# RS485.net
KiCad netlist of a schematic drawn in Altium Designer
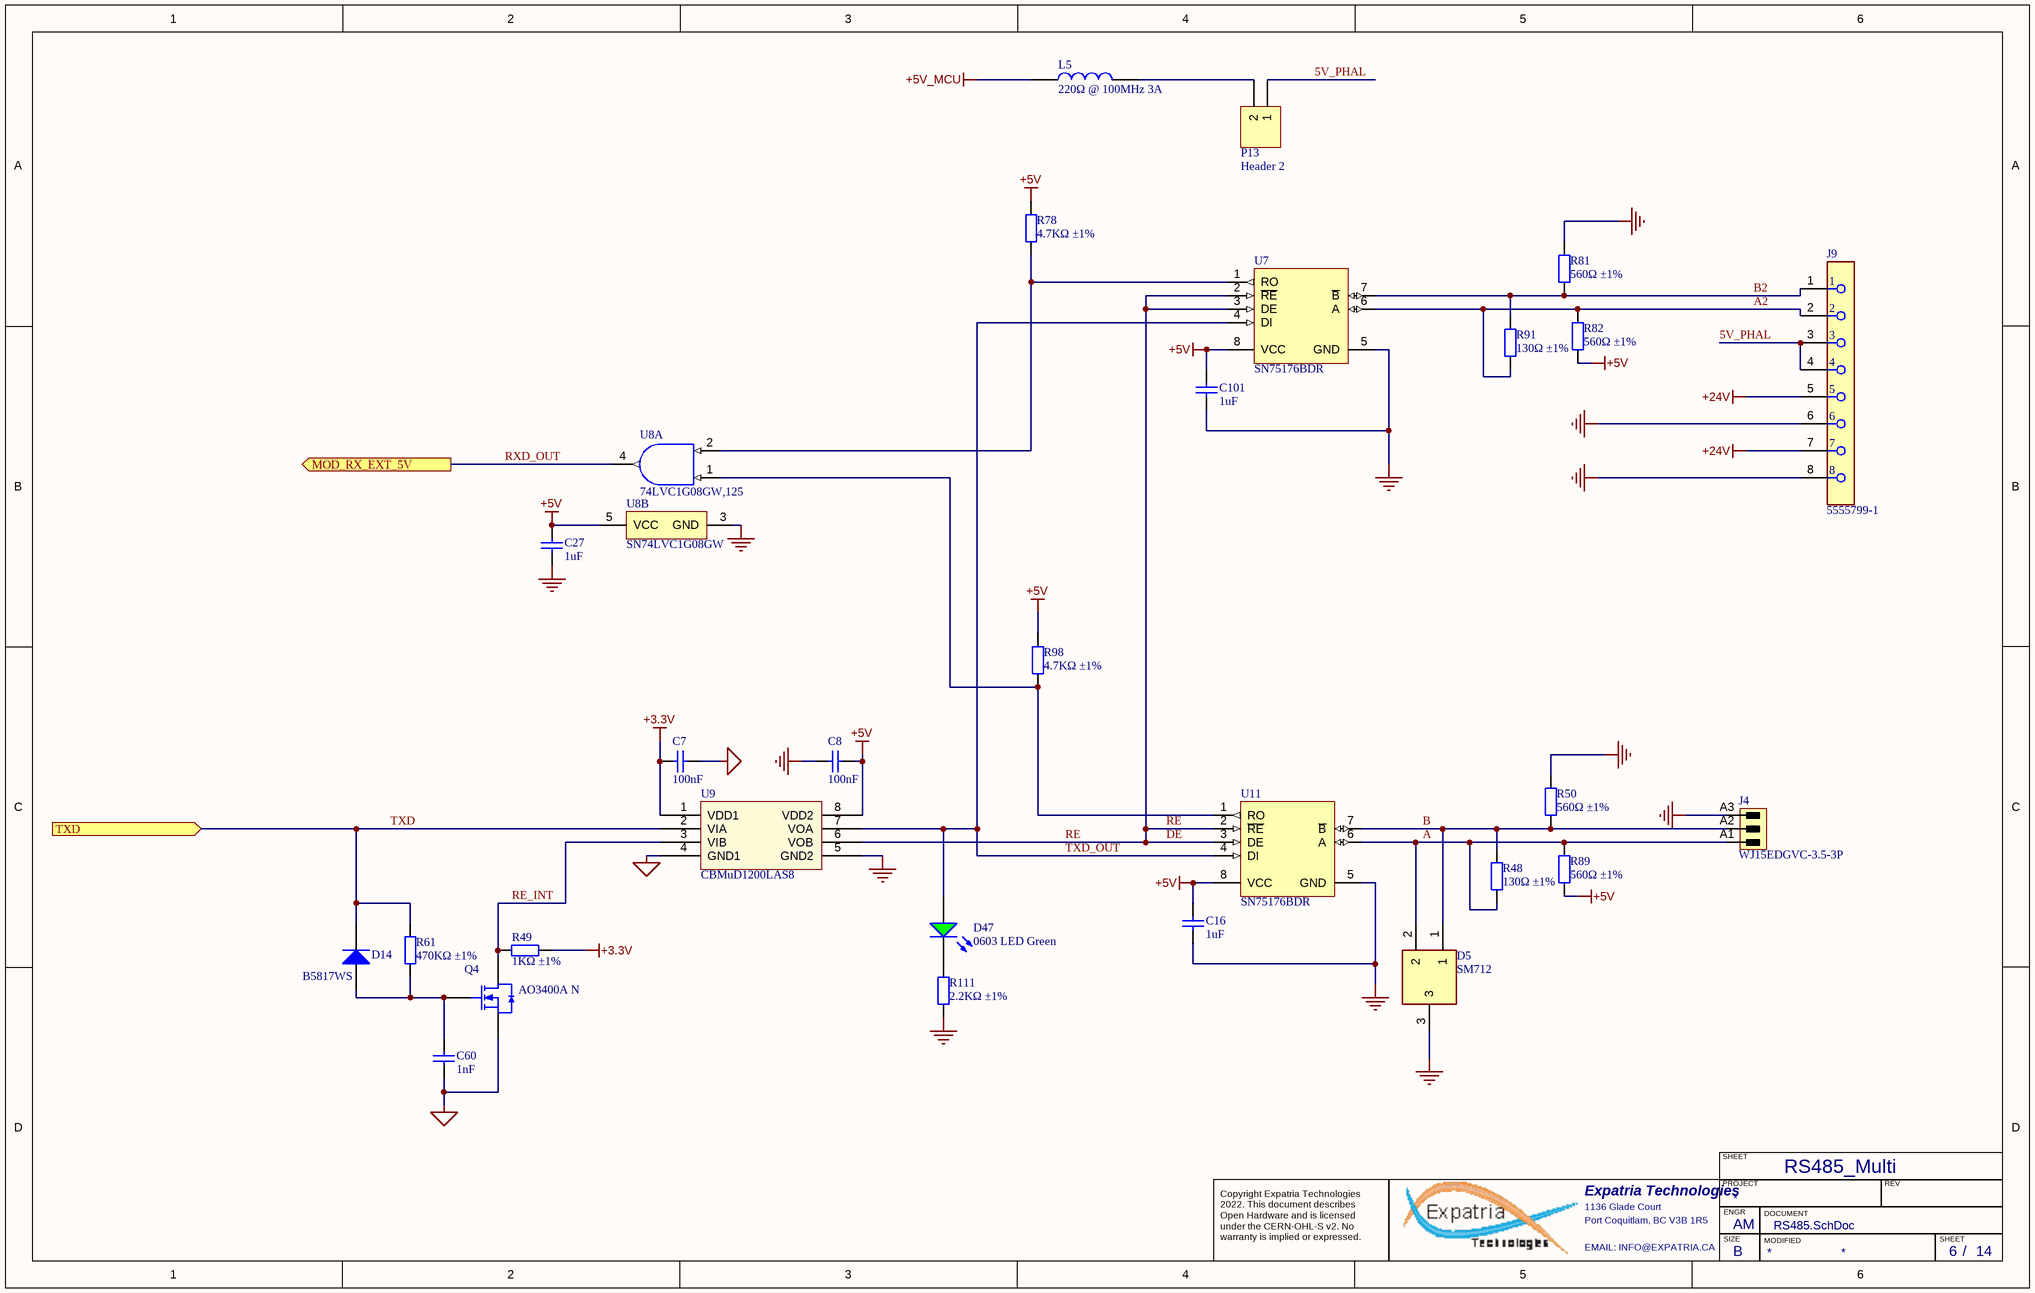
[diagram p0: RS485.SchDoc]

(export (version "E")
  (design (tool "Eeschema 10.0.6"))
  (components
    (comp (ref "C7")
      (value "100nF")
      (footprint "0402_C")
      (description "Chip capacitors")
      (fields
        (field (name "MANUFACTURER") "Samsung Electro-Mechanics")
        (field (name "PARTNUMBER") "CL05B104KO5NNNC")
      )
      (libsource (lib "Cap") (part "0402 100nF (104) 10% 16V"))
    )
    (comp (ref "C8")
      (value "100nF")
      (footprint "0402_C")
      (description "Chip capacitors")
      (fields
        (field (name "MANUFACTURER") "Samsung Electro-Mechanics")
        (field (name "PARTNUMBER") "CL05B104KO5NNNC")
      )
      (libsource (lib "Cap") (part "0402 100nF (104) 10% 16V"))
    )
    (comp (ref "C16")
      (value "1uF")
      (footprint "0603_C")
      (description "Chip capacitors")
      (fields
        (field (name "MANUFACTURER") "Samsung Electro-Mechanics")
        (field (name "PARTNUMBER") "CL10A105KB8NNNC")
      )
      (libsource (lib "Cap") (part "0603 1uF (105) 10% 50V"))
    )
    (comp (ref "C27")
      (value "1uF")
      (footprint "0603_C")
      (description "Chip capacitors")
      (fields
        (field (name "MANUFACTURER") "Samsung Electro-Mechanics")
        (field (name "PARTNUMBER") "CL10A105KB8NNNC")
      )
      (libsource (lib "Cap") (part "0603 1uF (105) 10% 50V"))
    )
    (comp (ref "C60")
      (value "1nF")
      (footprint "0603_C")
      (description "Chip capacitors")
      (fields
        (field (name "MANUFACTURER") "Samsung Electro-Mechanics")
        (field (name "PARTNUMBER") "CL10B102KB8NNNC")
      )
      (libsource (lib "Cap") (part "0603 1nF (102) 10% 50V"))
    )
    (comp (ref "C101")
      (value "1uF")
      (footprint "0603_C")
      (description "Chip capacitors")
      (fields
        (field (name "MANUFACTURER") "Samsung Electro-Mechanics")
        (field (name "PARTNUMBER") "CL10A105KB8NNNC")
      )
      (libsource (lib "Cap") (part "0603 1uF (105) 10% 50V"))
    )
    (comp (ref "D5")
      (value "SM712")
      (footprint "SamacSys:SOT95P230X117-3N")
      (description "Bidirectional 12V (Max), 7V (Max) 7.5V / 13.3V 10V / 20V 12A(8/20us) SOT-23-3 TVS RoHS")
      (libsource (lib "*") (part "CDSOT23-SM712"))
    )
    (comp (ref "D14")
      (value "B5817WS")
      (footprint "SOD-323")
      (description "20V 750mV@3A 1A SOD-323 Schottky Barrier Diodes (SBD) ROHS")
      (libsource (lib "Diode") (part "SOD-123 B5819W  SL"))
    )
    (comp (ref "D47")
      (value "0603 LED Green")
      (footprint "0603_LED_S1 - GREEN")
      (fields
        (field (name "MANUFACTURER PART NUMBER") "19-217/GHC-YR1S2/3T")
        (field (name "MANUFACTURER") "Everlight Elec")
      )
      (libsource (lib "Sienci_Labs") (part "19-217/GHC-YR1S2/3T"))
    )
    (comp (ref "J4")
      (value "WJ15EDGVC-3.5-3P")
      (footprint "691321100003 - 3.5mm  3p")
      (fields (field (name "MANUFACTURER") "Ningbo Kangnex Elec"))
      (libsource (lib "Universal_CNC_Breakout") (part "3.5mm Terminal Header 3p"))
    )
    (comp (ref "J9")
      (value "5555799-1")
      (footprint "FP-5555799-1-MFG")
      (description "CONN MOD JACK 8P8C VERT UNSHLD")
      (fields
        (field (name "MANUFACTURER") "TE Connectivity")
        (field (name "OCTOPART") "https://octopart.com/5555799-1-te+connectivity-39526335")
      )
      (libsource (lib "PrintNC_GRBLHAL_Breakout") (part "a32a9c29f5c2290c50060dfb8ad7212"))
    )
    (comp (ref "L5")
      (value "220Ω @ 100MHz 3A")
      (footprint "0805_C")
      (description "40mΩ ±25% 220Ω@100MHz 0805 Ferrite Beads ROHS")
      (libsource (lib "FBEAD") (part "0402 220R@100Mhz 0.1A"))
    )
    (comp (ref "P13")
      (value "Header 2")
      (footprint "HDR1X2")
      (description "Header, 2-Pin")
      (fields (field (name "PUBLISHER") "Altium Limited"))
      (libsource (lib "Miscellaneous Connectors") (part "Header 2"))
    )
    (comp (ref "Q4")
      (value "AO3400A N")
      (footprint "SOT-23-3L")
      (description "MOS(场效应管)")
      (libsource (lib "MOS") (part "AO3400A N道沟 X0YV1T SOT-23"))
    )
    (comp (ref "R48")
      (value "130Ω ±1%")
      (footprint "0603_R")
      (description "Chip resistor")
      (fields (field (name "MANUFACTURER") "Uniroyal Elec") (field (name "PARTNUMBER") "0603WAF1300T5E"))
      (libsource (lib "RES") (part "0603 130R (1300) 1%"))
    )
    (comp (ref "R49")
      (value "1KΩ ±1%")
      (footprint "0402_R")
      (description "Chip resistor")
      (fields (field (name "MANUFACTURER") "Uniroyal Elec") (field (name "PARTNUMBER") "0402WGF1001TCE"))
      (libsource (lib "RES") (part "0402 1K (1001) 1%"))
    )
    (comp (ref "R50")
      (value "560Ω ±1%")
      (footprint "0603_R")
      (description "Chip resistor")
      (fields (field (name "MANUFACTURER") "Uniroyal Elec") (field (name "PARTNUMBER") "0603WAF5600T5E"))
      (libsource (lib "RES") (part "0603 560R (5600) 1%"))
    )
    (comp (ref "R61")
      (value "470KΩ ±1%")
      (footprint "0603_R")
      (description "Chip resistor")
      (fields (field (name "MANUFACTURER") "Uniroyal Elec") (field (name "PARTNUMBER") "0603WAF4703T5E"))
      (libsource (lib "RES") (part "0603 470K (4703) 1%"))
    )
    (comp (ref "R78")
      (value "4.7KΩ ±1%")
      (footprint "0402_R")
      (description "Chip resistor")
      (fields (field (name "MANUFACTURER") "Uniroyal Elec") (field (name "PARTNUMBER") "0402WGF4701TCE"))
      (libsource (lib "RES") (part "0402 4.7K (4701) 1%"))
    )
    (comp (ref "R81")
      (value "560Ω ±1%")
      (footprint "0603_R")
      (description "Chip resistor")
      (fields (field (name "MANUFACTURER") "Uniroyal Elec") (field (name "PARTNUMBER") "0603WAF5600T5E"))
      (libsource (lib "RES") (part "0603 560R (5600) 1%"))
    )
    (comp (ref "R82")
      (value "560Ω ±1%")
      (footprint "0603_R")
      (description "Chip resistor")
      (fields (field (name "MANUFACTURER") "Uniroyal Elec") (field (name "PARTNUMBER") "0603WAF5600T5E"))
      (libsource (lib "RES") (part "0603 560R (5600) 1%"))
    )
    (comp (ref "R89")
      (value "560Ω ±1%")
      (footprint "0603_R")
      (description "Chip resistor")
      (fields (field (name "MANUFACTURER") "Uniroyal Elec") (field (name "PARTNUMBER") "0603WAF5600T5E"))
      (libsource (lib "RES") (part "0603 560R (5600) 1%"))
    )
    (comp (ref "R91")
      (value "130Ω ±1%")
      (footprint "0603_R")
      (description "Chip resistor")
      (fields (field (name "MANUFACTURER") "Uniroyal Elec") (field (name "PARTNUMBER") "0603WAF1300T5E"))
      (libsource (lib "RES") (part "0603 130R (1300) 1%"))
    )
    (comp (ref "R98")
      (value "4.7KΩ ±1%")
      (footprint "0402_R")
      (description "Chip resistor")
      (fields (field (name "MANUFACTURER") "Uniroyal Elec") (field (name "PARTNUMBER") "0402WGF4701TCE"))
      (libsource (lib "RES") (part "0402 4.7K (4701) 1%"))
    )
    (comp (ref "R111")
      (value "2.2KΩ ±1%")
      (footprint "0402_R")
      (description "Chip resistor")
      (fields (field (name "MANUFACTURER") "Uniroyal Elec") (field (name "POWER") "1/16W"))
      (libsource (lib "RES") (part "0402 2.2K (2201) 1%"))
    )
    (comp (ref "U7")
      (value "SN75176BDR")
      (footprint "SOIC-8_150mil")
      (description "RS-485/RS-422")
      (libsource (lib "IC") (part "SN75176BDR_[C7063]"))
    )
    (comp (ref "U8")
      (value "74LVC1G08GW,125")
      (footprint "DCK0005A_M")
      (description "Single 2-Input Positive-AND Gate, DCK0005A")
      (fields (field (name "GENERIC PART NUMBER") "SN74LVC1G08") (field (name "MANUFACTURER") "Nexperia"))
      (libsource (lib "") (part "TI-SN74XXX1X08-5_1"))
    )
    (comp (ref "U9")
      (value "CBMuD1200LAS8")
      (footprint "SOIC-8_150mil")
      (description "Dual Channel Isolator")
      (libsource (lib "IC") (part "CBMuD1200LAS8"))
    )
    (comp (ref "U11")
      (value "SN75176BDR")
      (footprint "SOIC-8_150mil")
      (description "RS-485/RS-422")
      (libsource (lib "IC") (part "SN75176BDR_[C7063]"))
    )
  )
  (nets
    (net (code "1") (name "+3.3V") (class "Default")
      (node (ref "C7") (pin "1") (pinfunction "1_1") (pintype "passive"))
      (node (ref "R49") (pin "1") (pinfunction "1_1") (pintype "passive"))
      (node (ref "U9") (pin "1") (pinfunction "VDD1_1") (pintype "passive"))
    )
    (net (code "2") (name "+5V") (class "Default")
      (node (ref "C101") (pin "2") (pinfunction "2_2") (pintype "passive"))
      (node (ref "C16") (pin "2") (pinfunction "2_2") (pintype "passive"))
      (node (ref "C27") (pin "2") (pinfunction "2_2") (pintype "passive"))
      (node (ref "C8") (pin "2") (pinfunction "2_2") (pintype "passive"))
      (node (ref "R78") (pin "2") (pinfunction "2_2") (pintype "passive"))
      (node (ref "R82") (pin "2") (pinfunction "2_2") (pintype "passive"))
      (node (ref "R89") (pin "2") (pinfunction "2_2") (pintype "passive"))
      (node (ref "R98") (pin "2") (pinfunction "2_2") (pintype "passive"))
      (node (ref "U11") (pin "8") (pinfunction "VCC_8") (pintype "power_in"))
      (node (ref "U7") (pin "8") (pinfunction "VCC_8") (pintype "power_in"))
      (node (ref "U8") (pin "5") (pinfunction "VCC_5") (pintype "power_in"))
      (node (ref "U9") (pin "8") (pinfunction "VDD2_8") (pintype "passive"))
    )
    (net (code "3") (name "+5V_MCU") (class "Default")
      (node (ref "L5") (pin "1") (pinfunction "1_1") (pintype "passive"))
    )
    (net (code "4") (name "+24V") (class "Default")
      (node (ref "J9") (pin "5") (pinfunction "5_5") (pintype "passive"))
      (node (ref "J9") (pin "7") (pinfunction "7_7") (pintype "passive"))
    )
    (net (code "5") (name "/5V_PHAL") (class "Default")
      (node (ref "J9") (pin "3") (pinfunction "3_3") (pintype "passive"))
      (node (ref "J9") (pin "4") (pinfunction "4_4") (pintype "passive"))
      (node (ref "P13") (pin "1") (pinfunction "1_1") (pintype "passive"))
    )
    (net (code "6") (name "/A") (class "Default")
      (node (ref "D5") (pin "2") (pinfunction "2_2") (pintype "passive"))
      (node (ref "J4") (pin "A1") (pinfunction "A1_A1") (pintype "passive"))
      (node (ref "R48") (pin "1") (pinfunction "1_1") (pintype "passive"))
      (node (ref "R89") (pin "1") (pinfunction "1_1") (pintype "passive"))
      (node (ref "U11") (pin "6") (pinfunction "A_6") (pintype "bidirectional"))
    )
    (net (code "7") (name "/A2") (class "Default")
      (node (ref "J9") (pin "2") (pinfunction "2_2") (pintype "passive"))
      (node (ref "R82") (pin "1") (pinfunction "1_1") (pintype "passive"))
      (node (ref "R91") (pin "1") (pinfunction "1_1") (pintype "passive"))
      (node (ref "U7") (pin "6") (pinfunction "A_6") (pintype "bidirectional"))
    )
    (net (code "8") (name "/B") (class "Default")
      (node (ref "D5") (pin "1") (pinfunction "1_1") (pintype "passive"))
      (node (ref "J4") (pin "A2") (pinfunction "A2_A2") (pintype "passive"))
      (node (ref "R48") (pin "2") (pinfunction "2_2") (pintype "passive"))
      (node (ref "R50") (pin "2") (pinfunction "2_2") (pintype "passive"))
      (node (ref "U11") (pin "7") (pinfunction "~{B}_7") (pintype "bidirectional"))
    )
    (net (code "9") (name "/B2") (class "Default")
      (node (ref "J9") (pin "1") (pinfunction "1_1") (pintype "passive"))
      (node (ref "R81") (pin "2") (pinfunction "2_2") (pintype "passive"))
      (node (ref "R91") (pin "2") (pinfunction "2_2") (pintype "passive"))
      (node (ref "U7") (pin "7") (pinfunction "~{B}_7") (pintype "bidirectional"))
    )
    (net (code "10") (name "/DE") (class "Default")
      (node (ref "U11") (pin "2") (pinfunction "~{RE}_2") (pintype "input"))
      (node (ref "U11") (pin "3") (pinfunction "DE_3") (pintype "input"))
      (node (ref "U7") (pin "2") (pinfunction "~{RE}_2") (pintype "input"))
      (node (ref "U7") (pin "3") (pinfunction "DE_3") (pintype "input"))
      (node (ref "U9") (pin "6") (pinfunction "VOB_6") (pintype "passive"))
    )
    (net (code "11") (name "/RE_INT") (class "Default")
      (node (ref "Q4") (pin "3") (pinfunction "D_3") (pintype "passive"))
      (node (ref "R49") (pin "2") (pinfunction "2_2") (pintype "passive"))
      (node (ref "U9") (pin "3") (pinfunction "VIB_3") (pintype "passive"))
    )
    (net (code "12") (name "/RXD_OUT") (class "Default")
      (node (ref "U8") (pin "4") (pinfunction "Y_4") (pintype "output"))
    )
    (net (code "13") (name "/TXD") (class "Default")
      (node (ref "D14") (pin "2") (pinfunction "K_2") (pintype "passive"))
      (node (ref "R61") (pin "1") (pinfunction "1_1") (pintype "passive"))
      (node (ref "U9") (pin "2") (pinfunction "VIA_2") (pintype "passive"))
    )
    (net (code "14") (name "/TXD_OUT") (class "Default")
      (node (ref "D47") (pin "A") (pinfunction "A_A") (pintype "passive"))
      (node (ref "U11") (pin "4") (pinfunction "DI_4") (pintype "input"))
      (node (ref "U7") (pin "4") (pinfunction "DI_4") (pintype "input"))
      (node (ref "U9") (pin "7") (pinfunction "VOA_7") (pintype "passive"))
    )
    (net (code "15") (name "GND") (class "Default")
      (node (ref "C101") (pin "1") (pinfunction "1_1") (pintype "passive"))
      (node (ref "C16") (pin "1") (pinfunction "1_1") (pintype "passive"))
      (node (ref "C27") (pin "1") (pinfunction "1_1") (pintype "passive"))
      (node (ref "C8") (pin "1") (pinfunction "1_1") (pintype "passive"))
      (node (ref "D5") (pin "3") (pinfunction "3_3") (pintype "passive"))
      (node (ref "J4") (pin "A3") (pinfunction "A3_A3") (pintype "passive"))
      (node (ref "J9") (pin "6") (pinfunction "6_6") (pintype "passive"))
      (node (ref "J9") (pin "8") (pinfunction "8_8") (pintype "passive"))
      (node (ref "R111") (pin "1") (pinfunction "1_1") (pintype "passive"))
      (node (ref "R50") (pin "1") (pinfunction "1_1") (pintype "passive"))
      (node (ref "R81") (pin "1") (pinfunction "1_1") (pintype "passive"))
      (node (ref "U11") (pin "5") (pinfunction "GND_5") (pintype "power_in"))
      (node (ref "U7") (pin "5") (pinfunction "GND_5") (pintype "power_in"))
      (node (ref "U8") (pin "3") (pinfunction "GND_3") (pintype "power_in"))
      (node (ref "U9") (pin "5") (pinfunction "GND2_5") (pintype "passive"))
    )
    (net (code "16") (name "MCU_GND") (class "Default")
      (node (ref "C60") (pin "2") (pinfunction "2_2") (pintype "passive"))
      (node (ref "C7") (pin "2") (pinfunction "2_2") (pintype "passive"))
      (node (ref "Q4") (pin "2") (pinfunction "S_2") (pintype "passive"))
      (node (ref "U9") (pin "4") (pinfunction "GND1_4") (pintype "passive"))
    )
    (net (code "17") (name "Net-(D14-A)") (class "Default")
      (node (ref "C60") (pin "1") (pinfunction "1_1") (pintype "passive"))
      (node (ref "D14") (pin "1") (pinfunction "A_1") (pintype "passive"))
      (node (ref "Q4") (pin "1") (pinfunction "G_1") (pintype "passive"))
      (node (ref "R61") (pin "2") (pinfunction "2_2") (pintype "passive"))
    )
    (net (code "18") (name "Net-(D47-PadK)") (class "Default")
      (node (ref "D47") (pin "K") (pinfunction "K_K") (pintype "passive"))
      (node (ref "R111") (pin "2") (pinfunction "2_2") (pintype "passive"))
    )
    (net (code "19") (name "Net-(L5-Pad2)") (class "Default")
      (node (ref "L5") (pin "2") (pinfunction "2_2") (pintype "passive"))
      (node (ref "P13") (pin "2") (pinfunction "2_2") (pintype "passive"))
    )
    (net (code "20") (name "Net-(U7-RO)") (class "Default")
      (node (ref "R78") (pin "1") (pinfunction "1_1") (pintype "passive"))
      (node (ref "U7") (pin "1") (pinfunction "RO_1") (pintype "output"))
      (node (ref "U8") (pin "2") (pinfunction "B_2") (pintype "input"))
    )
    (net (code "21") (name "Net-(U11-RO)") (class "Default")
      (node (ref "R98") (pin "1") (pinfunction "1_1") (pintype "passive"))
      (node (ref "U11") (pin "1") (pinfunction "RO_1") (pintype "output"))
      (node (ref "U8") (pin "1") (pinfunction "A_1") (pintype "input"))
    )
  )
)
